# treiber.net
KiCad netlist of a schematic drawn in EAGLE
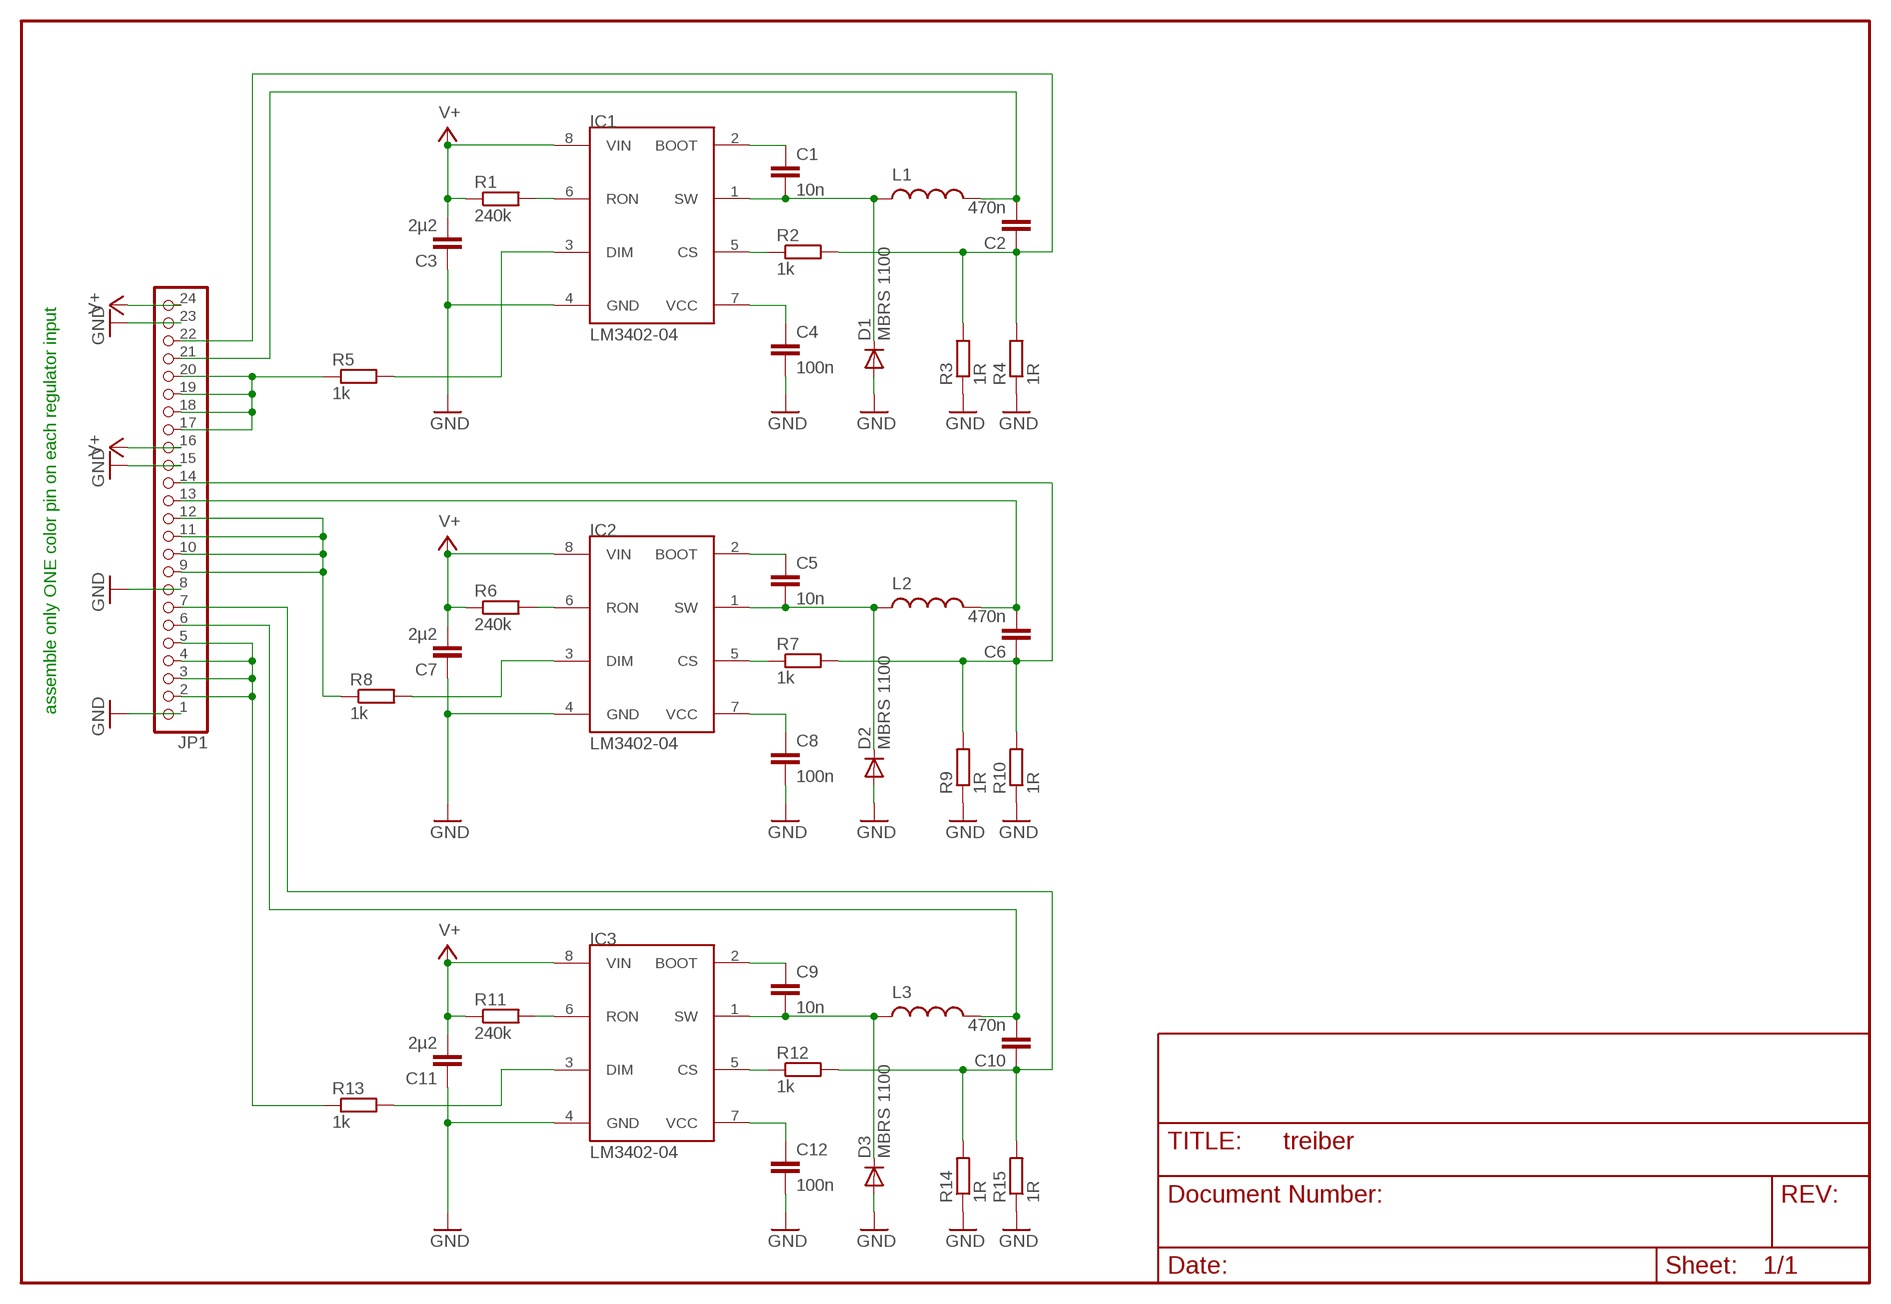
[diagram p0: schematic, sheet 1]

(export (version "E")
  (design (tool "Eeschema 10.0.6"))
  (components
    (comp (ref "C1")
      (value "10n")
      (footprint "eagle-import:C1206K")
      (libsource (lib "eagle-import") (part "C-EUC1206K"))
    )
    (comp (ref "C2")
      (value "470n")
      (footprint "eagle-import:C1206K")
      (libsource (lib "eagle-import") (part "C-EUC1206K"))
    )
    (comp (ref "C3")
      (value "2µ2")
      (footprint "eagle-import:C1206K")
      (libsource (lib "eagle-import") (part "C-EUC1206K"))
    )
    (comp (ref "C4")
      (value "100n")
      (footprint "eagle-import:C1206K")
      (libsource (lib "eagle-import") (part "C-EUC1206K"))
    )
    (comp (ref "C5")
      (value "10n")
      (footprint "eagle-import:C1206K")
      (libsource (lib "eagle-import") (part "C-EUC1206K"))
    )
    (comp (ref "C6")
      (value "470n")
      (footprint "eagle-import:C1206K")
      (libsource (lib "eagle-import") (part "C-EUC1206K"))
    )
    (comp (ref "C7")
      (value "2µ2")
      (footprint "eagle-import:C1206K")
      (libsource (lib "eagle-import") (part "C-EUC1206K"))
    )
    (comp (ref "C8")
      (value "100n")
      (footprint "eagle-import:C1206K")
      (libsource (lib "eagle-import") (part "C-EUC1206K"))
    )
    (comp (ref "C9")
      (value "10n")
      (footprint "eagle-import:C1206K")
      (libsource (lib "eagle-import") (part "C-EUC1206K"))
    )
    (comp (ref "C10")
      (value "470n")
      (footprint "eagle-import:C1206K")
      (libsource (lib "eagle-import") (part "C-EUC1206K"))
    )
    (comp (ref "C11")
      (value "2µ2")
      (footprint "eagle-import:C1206K")
      (libsource (lib "eagle-import") (part "C-EUC1206K"))
    )
    (comp (ref "C12")
      (value "100n")
      (footprint "eagle-import:C1206K")
      (libsource (lib "eagle-import") (part "C-EUC1206K"))
    )
    (comp (ref "D1")
      (value "MBRS 1100")
      (footprint "eagle-import:DO214AA")
      (libsource (lib "eagle-import") (part "DIODE-"))
    )
    (comp (ref "D2")
      (value "MBRS 1100")
      (footprint "eagle-import:DO214AA")
      (libsource (lib "eagle-import") (part "DIODE-"))
    )
    (comp (ref "D3")
      (value "MBRS 1100")
      (footprint "eagle-import:DO214AA")
      (libsource (lib "eagle-import") (part "DIODE-"))
    )
    (comp (ref "IC1")
      (value "LM3402-04")
      (footprint "eagle-import:SOP08")
      (libsource (lib "eagle-import") (part "LM3402-04"))
    )
    (comp (ref "IC2")
      (value "LM3402-04")
      (footprint "eagle-import:SOP08")
      (libsource (lib "eagle-import") (part "LM3402-04"))
    )
    (comp (ref "IC3")
      (value "LM3402-04")
      (footprint "eagle-import:SOP08")
      (libsource (lib "eagle-import") (part "LM3402-04"))
    )
    (comp (ref "JP1")
      (value "PINHD-1X24_2.54-SMD-90°")
      (footprint "eagle-import:1X24SMD_90")
      (libsource (lib "eagle-import") (part "PINHD-1X24_2.54-SMD-90°"))
    )
    (comp (ref "L1")
      (value "PIS4720")
      (footprint "eagle-import:PIS")
      (libsource (lib "eagle-import") (part "PIS4720"))
    )
    (comp (ref "L2")
      (value "PIS4720")
      (footprint "eagle-import:PIS")
      (libsource (lib "eagle-import") (part "PIS4720"))
    )
    (comp (ref "L3")
      (value "PIS4720")
      (footprint "eagle-import:PIS")
      (libsource (lib "eagle-import") (part "PIS4720"))
    )
    (comp (ref "R1")
      (value "240k")
      (footprint "eagle-import:R0805W")
      (libsource (lib "eagle-import") (part "R-EU_R0805W"))
    )
    (comp (ref "R2")
      (value "1k")
      (footprint "eagle-import:R1210W")
      (libsource (lib "eagle-import") (part "R-EU_R1210W"))
    )
    (comp (ref "R3")
      (value "1R")
      (footprint "eagle-import:R1210W")
      (libsource (lib "eagle-import") (part "R-EU_R1210W"))
    )
    (comp (ref "R4")
      (value "1R")
      (footprint "eagle-import:R1210W")
      (libsource (lib "eagle-import") (part "R-EU_R1210W"))
    )
    (comp (ref "R5")
      (value "1k")
      (footprint "eagle-import:R1210W")
      (libsource (lib "eagle-import") (part "R-EU_R1210W"))
    )
    (comp (ref "R6")
      (value "240k")
      (footprint "eagle-import:R0805W")
      (libsource (lib "eagle-import") (part "R-EU_R0805W"))
    )
    (comp (ref "R7")
      (value "1k")
      (footprint "eagle-import:R1210W")
      (libsource (lib "eagle-import") (part "R-EU_R1210W"))
    )
    (comp (ref "R8")
      (value "1k")
      (footprint "eagle-import:R1210W")
      (libsource (lib "eagle-import") (part "R-EU_R1210W"))
    )
    (comp (ref "R9")
      (value "1R")
      (footprint "eagle-import:R1210W")
      (libsource (lib "eagle-import") (part "R-EU_R1210W"))
    )
    (comp (ref "R10")
      (value "1R")
      (footprint "eagle-import:R1210W")
      (libsource (lib "eagle-import") (part "R-EU_R1210W"))
    )
    (comp (ref "R11")
      (value "240k")
      (footprint "eagle-import:R0805W")
      (libsource (lib "eagle-import") (part "R-EU_R0805W"))
    )
    (comp (ref "R12")
      (value "1k")
      (footprint "eagle-import:R1210W")
      (libsource (lib "eagle-import") (part "R-EU_R1210W"))
    )
    (comp (ref "R13")
      (value "1k")
      (footprint "eagle-import:R1210W")
      (libsource (lib "eagle-import") (part "R-EU_R1210W"))
    )
    (comp (ref "R14")
      (value "1R")
      (footprint "eagle-import:R1210W")
      (libsource (lib "eagle-import") (part "R-EU_R1210W"))
    )
    (comp (ref "R15")
      (value "1R")
      (footprint "eagle-import:R1210W")
      (libsource (lib "eagle-import") (part "R-EU_R1210W"))
    )
  )
  (nets
    (net (code "1") (name "GND") (class "Default")
      (node (ref "C11") (pin "1") (pinfunction "1_1") (pintype "passive"))
      (node (ref "C12") (pin "2") (pinfunction "2_2") (pintype "passive"))
      (node (ref "C3") (pin "1") (pinfunction "1_1") (pintype "passive"))
      (node (ref "C4") (pin "2") (pinfunction "2_2") (pintype "passive"))
      (node (ref "C7") (pin "1") (pinfunction "1_1") (pintype "passive"))
      (node (ref "C8") (pin "2") (pinfunction "2_2") (pintype "passive"))
      (node (ref "D1") (pin "A") (pinfunction "A_A") (pintype "passive"))
      (node (ref "D2") (pin "A") (pinfunction "A_A") (pintype "passive"))
      (node (ref "D3") (pin "A") (pinfunction "A_A") (pintype "passive"))
      (node (ref "IC1") (pin "4") (pinfunction "GND_4") (pintype "bidirectional"))
      (node (ref "IC2") (pin "4") (pinfunction "GND_4") (pintype "bidirectional"))
      (node (ref "IC3") (pin "4") (pinfunction "GND_4") (pintype "bidirectional"))
      (node (ref "JP1") (pin "1") (pinfunction "1_1") (pintype "passive"))
      (node (ref "JP1") (pin "15") (pinfunction "15_15") (pintype "passive"))
      (node (ref "JP1") (pin "23") (pinfunction "23_23") (pintype "passive"))
      (node (ref "JP1") (pin "8") (pinfunction "8_8") (pintype "passive"))
      (node (ref "R10") (pin "1") (pinfunction "1_1") (pintype "passive"))
      (node (ref "R14") (pin "1") (pinfunction "1_1") (pintype "passive"))
      (node (ref "R15") (pin "1") (pinfunction "1_1") (pintype "passive"))
      (node (ref "R3") (pin "1") (pinfunction "1_1") (pintype "passive"))
      (node (ref "R4") (pin "1") (pinfunction "1_1") (pintype "passive"))
      (node (ref "R9") (pin "1") (pinfunction "1_1") (pintype "passive"))
    )
    (net (code "2") (name "Net-(C2-Pad1)") (class "Default")
      (node (ref "C2") (pin "1") (pinfunction "1_1") (pintype "passive"))
      (node (ref "JP1") (pin "22") (pinfunction "22_22") (pintype "passive"))
      (node (ref "R2") (pin "2") (pinfunction "2_2") (pintype "passive"))
      (node (ref "R3") (pin "2") (pinfunction "2_2") (pintype "passive"))
      (node (ref "R4") (pin "2") (pinfunction "2_2") (pintype "passive"))
    )
    (net (code "3") (name "Net-(C2-Pad2)") (class "Default")
      (node (ref "C2") (pin "2") (pinfunction "2_2") (pintype "passive"))
      (node (ref "JP1") (pin "21") (pinfunction "21_21") (pintype "passive"))
      (node (ref "L1") (pin "P$1") (pinfunction "P$1_P$1") (pintype "passive"))
    )
    (net (code "4") (name "Net-(C6-Pad1)") (class "Default")
      (node (ref "C6") (pin "1") (pinfunction "1_1") (pintype "passive"))
      (node (ref "JP1") (pin "14") (pinfunction "14_14") (pintype "passive"))
      (node (ref "R10") (pin "2") (pinfunction "2_2") (pintype "passive"))
      (node (ref "R7") (pin "2") (pinfunction "2_2") (pintype "passive"))
      (node (ref "R9") (pin "2") (pinfunction "2_2") (pintype "passive"))
    )
    (net (code "5") (name "Net-(C6-Pad2)") (class "Default")
      (node (ref "C6") (pin "2") (pinfunction "2_2") (pintype "passive"))
      (node (ref "JP1") (pin "13") (pinfunction "13_13") (pintype "passive"))
      (node (ref "L2") (pin "P$1") (pinfunction "P$1_P$1") (pintype "passive"))
    )
    (net (code "6") (name "Net-(C10-Pad1)") (class "Default")
      (node (ref "C10") (pin "1") (pinfunction "1_1") (pintype "passive"))
      (node (ref "JP1") (pin "7") (pinfunction "7_7") (pintype "passive"))
      (node (ref "R12") (pin "2") (pinfunction "2_2") (pintype "passive"))
      (node (ref "R14") (pin "2") (pinfunction "2_2") (pintype "passive"))
      (node (ref "R15") (pin "2") (pinfunction "2_2") (pintype "passive"))
    )
    (net (code "7") (name "Net-(C10-Pad2)") (class "Default")
      (node (ref "C10") (pin "2") (pinfunction "2_2") (pintype "passive"))
      (node (ref "JP1") (pin "6") (pinfunction "6_6") (pintype "passive"))
      (node (ref "L3") (pin "P$1") (pinfunction "P$1_P$1") (pintype "passive"))
    )
    (net (code "8") (name "Net-(IC1-BOOT)") (class "Default")
      (node (ref "C1") (pin "1") (pinfunction "1_1") (pintype "passive"))
      (node (ref "IC1") (pin "2") (pinfunction "BOOT_2") (pintype "bidirectional"))
    )
    (net (code "9") (name "Net-(IC1-CS)") (class "Default")
      (node (ref "IC1") (pin "5") (pinfunction "CS_5") (pintype "bidirectional"))
      (node (ref "R2") (pin "1") (pinfunction "1_1") (pintype "passive"))
    )
    (net (code "10") (name "Net-(IC1-DIM)") (class "Default")
      (node (ref "IC1") (pin "3") (pinfunction "DIM_3") (pintype "bidirectional"))
      (node (ref "R5") (pin "2") (pinfunction "2_2") (pintype "passive"))
    )
    (net (code "11") (name "Net-(IC1-RON)") (class "Default")
      (node (ref "IC1") (pin "6") (pinfunction "RON_6") (pintype "bidirectional"))
      (node (ref "R1") (pin "2") (pinfunction "2_2") (pintype "passive"))
    )
    (net (code "12") (name "Net-(IC1-SW)") (class "Default")
      (node (ref "C1") (pin "2") (pinfunction "2_2") (pintype "passive"))
      (node (ref "D1") (pin "C") (pinfunction "C_C") (pintype "passive"))
      (node (ref "IC1") (pin "1") (pinfunction "SW_1") (pintype "bidirectional"))
      (node (ref "L1") (pin "P$2") (pinfunction "P$2_P$2") (pintype "passive"))
    )
    (net (code "13") (name "Net-(IC1-VCC)") (class "Default")
      (node (ref "C4") (pin "1") (pinfunction "1_1") (pintype "passive"))
      (node (ref "IC1") (pin "7") (pinfunction "VCC_7") (pintype "bidirectional"))
    )
    (net (code "14") (name "Net-(IC2-BOOT)") (class "Default")
      (node (ref "C5") (pin "1") (pinfunction "1_1") (pintype "passive"))
      (node (ref "IC2") (pin "2") (pinfunction "BOOT_2") (pintype "bidirectional"))
    )
    (net (code "15") (name "Net-(IC2-CS)") (class "Default")
      (node (ref "IC2") (pin "5") (pinfunction "CS_5") (pintype "bidirectional"))
      (node (ref "R7") (pin "1") (pinfunction "1_1") (pintype "passive"))
    )
    (net (code "16") (name "Net-(IC2-DIM)") (class "Default")
      (node (ref "IC2") (pin "3") (pinfunction "DIM_3") (pintype "bidirectional"))
      (node (ref "R8") (pin "2") (pinfunction "2_2") (pintype "passive"))
    )
    (net (code "17") (name "Net-(IC2-RON)") (class "Default")
      (node (ref "IC2") (pin "6") (pinfunction "RON_6") (pintype "bidirectional"))
      (node (ref "R6") (pin "2") (pinfunction "2_2") (pintype "passive"))
    )
    (net (code "18") (name "Net-(IC2-SW)") (class "Default")
      (node (ref "C5") (pin "2") (pinfunction "2_2") (pintype "passive"))
      (node (ref "D2") (pin "C") (pinfunction "C_C") (pintype "passive"))
      (node (ref "IC2") (pin "1") (pinfunction "SW_1") (pintype "bidirectional"))
      (node (ref "L2") (pin "P$2") (pinfunction "P$2_P$2") (pintype "passive"))
    )
    (net (code "19") (name "Net-(IC2-VCC)") (class "Default")
      (node (ref "C8") (pin "1") (pinfunction "1_1") (pintype "passive"))
      (node (ref "IC2") (pin "7") (pinfunction "VCC_7") (pintype "bidirectional"))
    )
    (net (code "20") (name "Net-(IC3-BOOT)") (class "Default")
      (node (ref "C9") (pin "1") (pinfunction "1_1") (pintype "passive"))
      (node (ref "IC3") (pin "2") (pinfunction "BOOT_2") (pintype "bidirectional"))
    )
    (net (code "21") (name "Net-(IC3-CS)") (class "Default")
      (node (ref "IC3") (pin "5") (pinfunction "CS_5") (pintype "bidirectional"))
      (node (ref "R12") (pin "1") (pinfunction "1_1") (pintype "passive"))
    )
    (net (code "22") (name "Net-(IC3-DIM)") (class "Default")
      (node (ref "IC3") (pin "3") (pinfunction "DIM_3") (pintype "bidirectional"))
      (node (ref "R13") (pin "2") (pinfunction "2_2") (pintype "passive"))
    )
    (net (code "23") (name "Net-(IC3-RON)") (class "Default")
      (node (ref "IC3") (pin "6") (pinfunction "RON_6") (pintype "bidirectional"))
      (node (ref "R11") (pin "2") (pinfunction "2_2") (pintype "passive"))
    )
    (net (code "24") (name "Net-(IC3-SW)") (class "Default")
      (node (ref "C9") (pin "2") (pinfunction "2_2") (pintype "passive"))
      (node (ref "D3") (pin "C") (pinfunction "C_C") (pintype "passive"))
      (node (ref "IC3") (pin "1") (pinfunction "SW_1") (pintype "bidirectional"))
      (node (ref "L3") (pin "P$2") (pinfunction "P$2_P$2") (pintype "passive"))
    )
    (net (code "25") (name "Net-(IC3-VCC)") (class "Default")
      (node (ref "C12") (pin "1") (pinfunction "1_1") (pintype "passive"))
      (node (ref "IC3") (pin "7") (pinfunction "VCC_7") (pintype "bidirectional"))
    )
    (net (code "26") (name "Net-(JP1-Pad2)") (class "Default")
      (node (ref "JP1") (pin "2") (pinfunction "2_2") (pintype "passive"))
      (node (ref "JP1") (pin "3") (pinfunction "3_3") (pintype "passive"))
      (node (ref "JP1") (pin "4") (pinfunction "4_4") (pintype "passive"))
      (node (ref "JP1") (pin "5") (pinfunction "5_5") (pintype "passive"))
      (node (ref "R13") (pin "1") (pinfunction "1_1") (pintype "passive"))
    )
    (net (code "27") (name "Net-(JP1-Pad10)") (class "Default")
      (node (ref "JP1") (pin "10") (pinfunction "10_10") (pintype "passive"))
      (node (ref "JP1") (pin "11") (pinfunction "11_11") (pintype "passive"))
      (node (ref "JP1") (pin "12") (pinfunction "12_12") (pintype "passive"))
      (node (ref "JP1") (pin "9") (pinfunction "9_9") (pintype "passive"))
      (node (ref "R8") (pin "1") (pinfunction "1_1") (pintype "passive"))
    )
    (net (code "28") (name "Net-(JP1-Pad17)") (class "Default")
      (node (ref "JP1") (pin "17") (pinfunction "17_17") (pintype "passive"))
      (node (ref "JP1") (pin "18") (pinfunction "18_18") (pintype "passive"))
      (node (ref "JP1") (pin "19") (pinfunction "19_19") (pintype "passive"))
      (node (ref "JP1") (pin "20") (pinfunction "20_20") (pintype "passive"))
      (node (ref "R5") (pin "1") (pinfunction "1_1") (pintype "passive"))
    )
    (net (code "29") (name "V+") (class "Default")
      (node (ref "C11") (pin "2") (pinfunction "2_2") (pintype "passive"))
      (node (ref "C3") (pin "2") (pinfunction "2_2") (pintype "passive"))
      (node (ref "C7") (pin "2") (pinfunction "2_2") (pintype "passive"))
      (node (ref "IC1") (pin "8") (pinfunction "VIN_8") (pintype "bidirectional"))
      (node (ref "IC2") (pin "8") (pinfunction "VIN_8") (pintype "bidirectional"))
      (node (ref "IC3") (pin "8") (pinfunction "VIN_8") (pintype "bidirectional"))
      (node (ref "JP1") (pin "16") (pinfunction "16_16") (pintype "passive"))
      (node (ref "JP1") (pin "24") (pinfunction "24_24") (pintype "passive"))
      (node (ref "R1") (pin "1") (pinfunction "1_1") (pintype "passive"))
      (node (ref "R11") (pin "1") (pinfunction "1_1") (pintype "passive"))
      (node (ref "R6") (pin "1") (pinfunction "1_1") (pintype "passive"))
    )
  )
)
